# STM32F303CBT6_BTN8962TA_V1_0.net
KiCad netlist of a schematic drawn in EAGLE
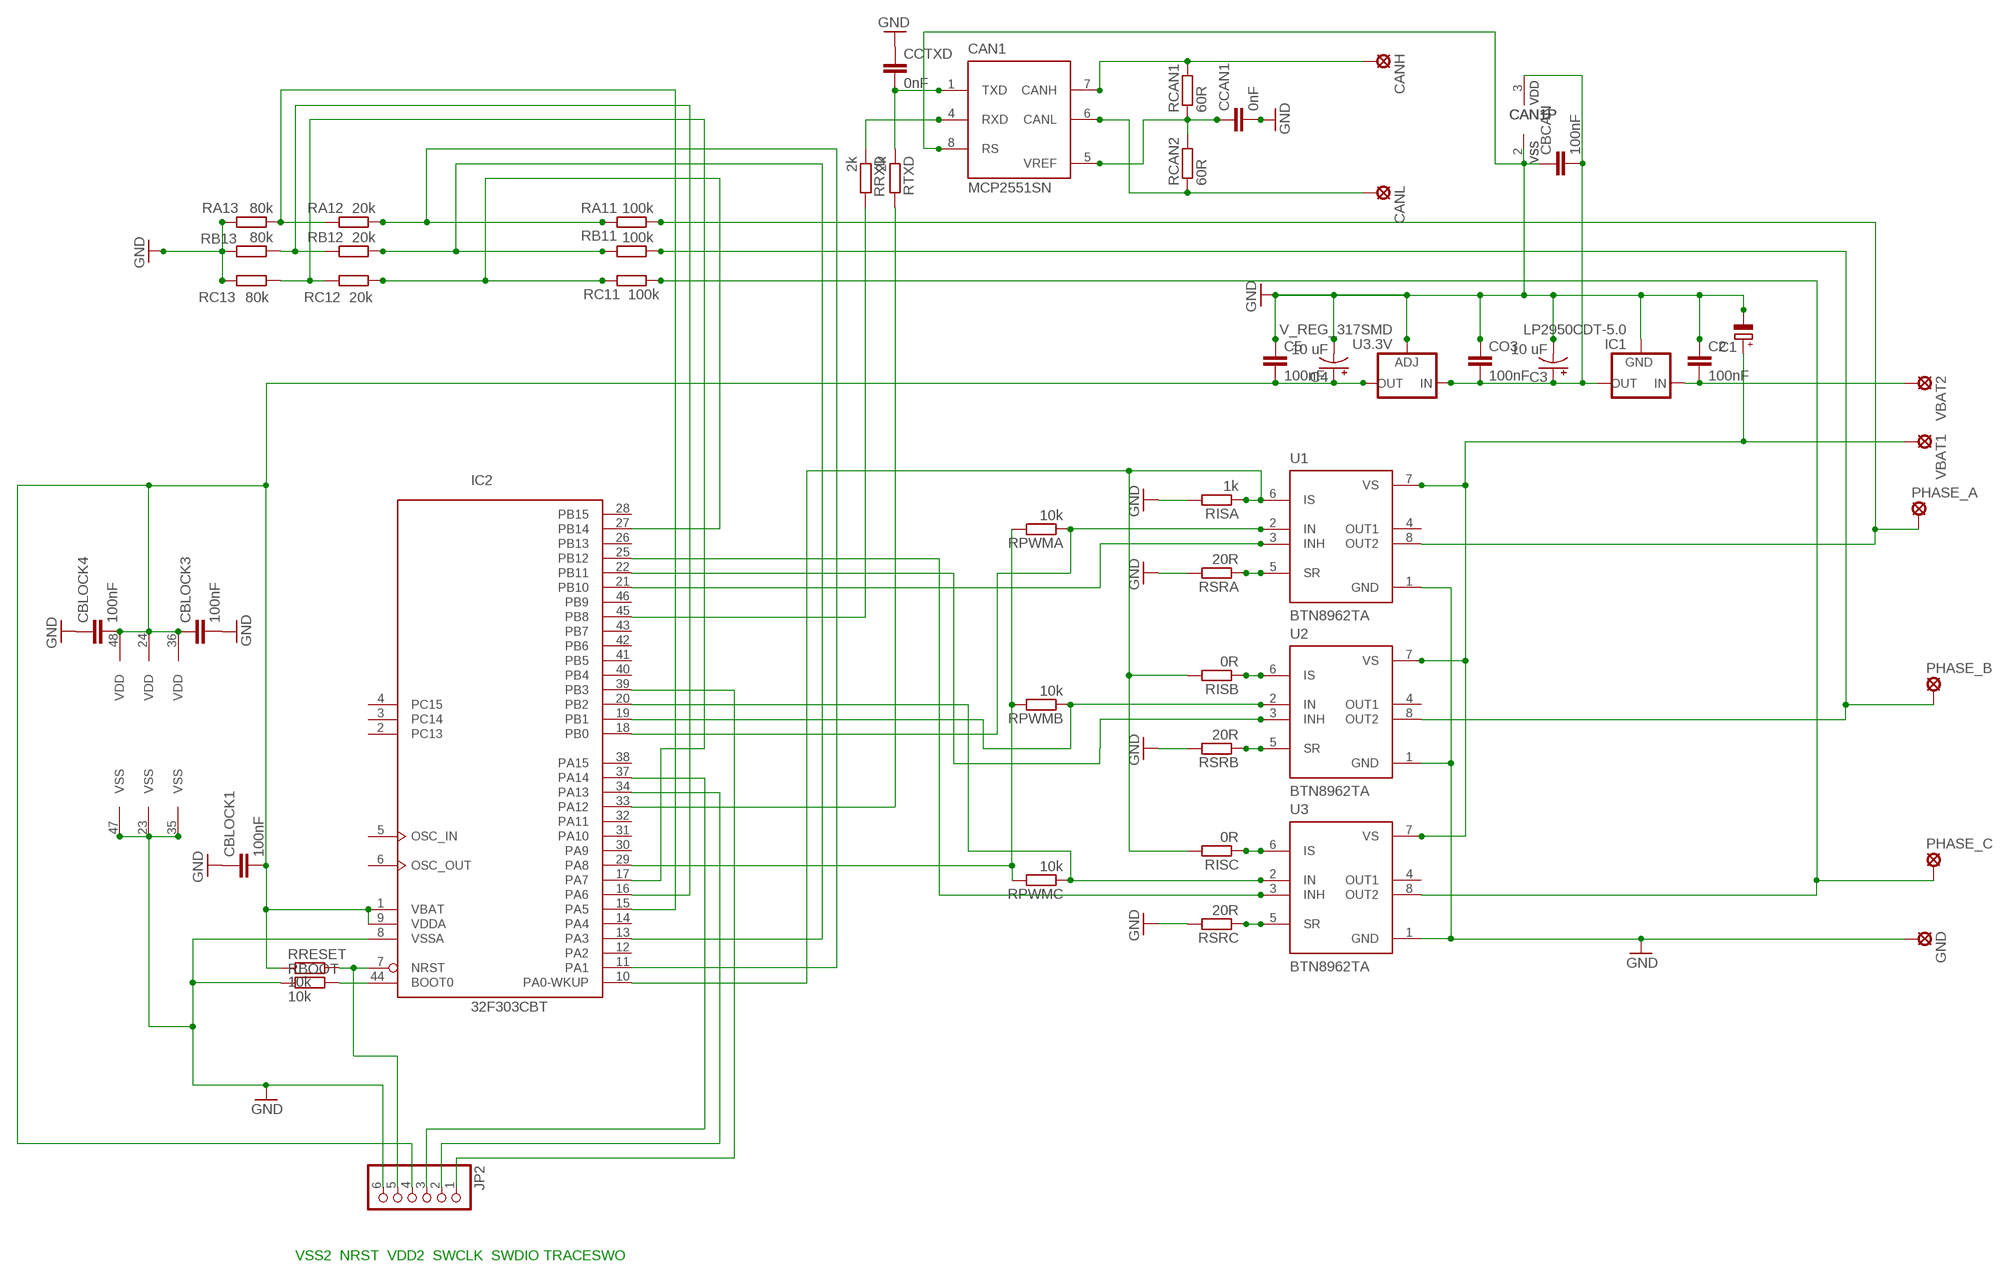
[diagram p0: schematic, sheet 1]

(export (version "E")
  (design (tool "Eeschema 10.0.6"))
  (components
    (comp (ref "C1")
      (value "CPOL-EUE3.5-10")
      (footprint "eagle-import:E3,5-10")
      (libsource (lib "eagle-import") (part "CPOL-EUE3.5-10"))
    )
    (comp (ref "C2")
      (value "100nF")
      (footprint "eagle-import:C0805")
      (libsource (lib "eagle-import") (part "C-EUC0805"))
    )
    (comp (ref "C3")
      (value "10 uF")
      (footprint "eagle-import:PANASONIC_D")
      (libsource (lib "eagle-import") (part "CAP_POLD"))
    )
    (comp (ref "C4")
      (value "10 uF")
      (footprint "eagle-import:PANASONIC_D")
      (libsource (lib "eagle-import") (part "CAP_POLD"))
    )
    (comp (ref "C5")
      (value "100nF")
      (footprint "eagle-import:C0805")
      (libsource (lib "eagle-import") (part "C-EUC0805"))
    )
    (comp (ref "CAN1")
      (value "MCP2551SN")
      (footprint "eagle-import:SO-08")
      (libsource (lib "eagle-import") (part "MCP2551SN"))
    )
    (comp (ref "CANH")
      (value "LSP10")
      (footprint "eagle-import:LSP10")
      (libsource (lib "eagle-import") (part "LSP10"))
    )
    (comp (ref "CANL")
      (value "LSP10")
      (footprint "eagle-import:LSP10")
      (libsource (lib "eagle-import") (part "LSP10"))
    )
    (comp (ref "CBCAN")
      (value "100nF")
      (footprint "eagle-import:C0805")
      (libsource (lib "eagle-import") (part "C-EUC0805"))
    )
    (comp (ref "CBLOCK1")
      (value "100nF")
      (footprint "eagle-import:C0805")
      (libsource (lib "eagle-import") (part "C-EUC0805"))
    )
    (comp (ref "CBLOCK3")
      (value "100nF")
      (footprint "eagle-import:C0805")
      (libsource (lib "eagle-import") (part "C-EUC0805"))
    )
    (comp (ref "CBLOCK4")
      (value "100nF")
      (footprint "eagle-import:C0805")
      (libsource (lib "eagle-import") (part "C-EUC0805"))
    )
    (comp (ref "CCAN1")
      (value "0nF")
      (footprint "eagle-import:C0805")
      (libsource (lib "eagle-import") (part "C-EUC0805"))
    )
    (comp (ref "CCTXD")
      (value "0nF")
      (footprint "eagle-import:C0805")
      (libsource (lib "eagle-import") (part "C-EUC0805"))
    )
    (comp (ref "CO3")
      (value "100nF")
      (footprint "eagle-import:C0805")
      (libsource (lib "eagle-import") (part "C-EUC0805"))
    )
    (comp (ref "GND")
      (value "SE14")
      (footprint "eagle-import:SE14")
      (libsource (lib "eagle-import") (part "SE14"))
    )
    (comp (ref "IC1")
      (value "LP2950CDT-5.0")
      (footprint "eagle-import:DPACK")
      (libsource (lib "eagle-import") (part "LP2950?CDT-5.0"))
    )
    (comp (ref "IC2")
      (value "32F303CBT")
      (footprint "eagle-import:LQFP48")
      (libsource (lib "eagle-import") (part "STM32F303CTB"))
    )
    (comp (ref "JP2")
      (value "PINHD-1X6")
      (footprint "eagle-import:1X06")
      (libsource (lib "eagle-import") (part "PINHD-1X6"))
    )
    (comp (ref "PHASE_A")
      (value "SE14")
      (footprint "eagle-import:SE14")
      (libsource (lib "eagle-import") (part "SE14"))
    )
    (comp (ref "PHASE_B")
      (value "SE14")
      (footprint "eagle-import:SE14")
      (libsource (lib "eagle-import") (part "SE14"))
    )
    (comp (ref "PHASE_C")
      (value "SE14")
      (footprint "eagle-import:SE14")
      (libsource (lib "eagle-import") (part "SE14"))
    )
    (comp (ref "RA11")
      (value "100k")
      (footprint "eagle-import:R0805")
      (libsource (lib "eagle-import") (part "R-EU_R0805"))
    )
    (comp (ref "RA12")
      (value "20k")
      (footprint "eagle-import:R0805")
      (libsource (lib "eagle-import") (part "R-EU_R0805"))
    )
    (comp (ref "RA13")
      (value "80k")
      (footprint "eagle-import:R0805")
      (libsource (lib "eagle-import") (part "R-EU_R0805"))
    )
    (comp (ref "RB11")
      (value "100k")
      (footprint "eagle-import:R0805")
      (libsource (lib "eagle-import") (part "R-EU_R0805"))
    )
    (comp (ref "RB12")
      (value "20k")
      (footprint "eagle-import:R0805")
      (libsource (lib "eagle-import") (part "R-EU_R0805"))
    )
    (comp (ref "RB13")
      (value "80k")
      (footprint "eagle-import:R0805")
      (libsource (lib "eagle-import") (part "R-EU_R0805"))
    )
    (comp (ref "RBOOT")
      (value "10k")
      (footprint "eagle-import:R0805")
      (libsource (lib "eagle-import") (part "R-EU_R0805"))
    )
    (comp (ref "RC11")
      (value "100k")
      (footprint "eagle-import:R0805")
      (libsource (lib "eagle-import") (part "R-EU_R0805"))
    )
    (comp (ref "RC12")
      (value "20k")
      (footprint "eagle-import:R0805")
      (libsource (lib "eagle-import") (part "R-EU_R0805"))
    )
    (comp (ref "RC13")
      (value "80k")
      (footprint "eagle-import:R0805")
      (libsource (lib "eagle-import") (part "R-EU_R0805"))
    )
    (comp (ref "RCAN1")
      (value "60R")
      (footprint "eagle-import:R0805")
      (libsource (lib "eagle-import") (part "R-EU_R0805"))
    )
    (comp (ref "RCAN2")
      (value "60R")
      (footprint "eagle-import:R0805")
      (libsource (lib "eagle-import") (part "R-EU_R0805"))
    )
    (comp (ref "RISA")
      (value "1k")
      (footprint "eagle-import:R0805")
      (libsource (lib "eagle-import") (part "R-EU_R0805"))
    )
    (comp (ref "RISB")
      (value "0R")
      (footprint "eagle-import:R0805")
      (libsource (lib "eagle-import") (part "R-EU_R0805"))
    )
    (comp (ref "RISC")
      (value "0R")
      (footprint "eagle-import:R0805")
      (libsource (lib "eagle-import") (part "R-EU_R0805"))
    )
    (comp (ref "RPWMA")
      (value "10k")
      (footprint "eagle-import:R0805")
      (libsource (lib "eagle-import") (part "R-EU_R0805"))
    )
    (comp (ref "RPWMB")
      (value "10k")
      (footprint "eagle-import:R0805")
      (libsource (lib "eagle-import") (part "R-EU_R0805"))
    )
    (comp (ref "RPWMC")
      (value "10k")
      (footprint "eagle-import:R0805")
      (libsource (lib "eagle-import") (part "R-EU_R0805"))
    )
    (comp (ref "RRESET")
      (value "10k")
      (footprint "eagle-import:R0805")
      (libsource (lib "eagle-import") (part "R-EU_R0805"))
    )
    (comp (ref "RRXD")
      (value "2k")
      (footprint "eagle-import:R0805")
      (libsource (lib "eagle-import") (part "R-EU_R0805"))
    )
    (comp (ref "RSRA")
      (value "20R")
      (footprint "eagle-import:R0805")
      (libsource (lib "eagle-import") (part "R-EU_R0805"))
    )
    (comp (ref "RSRB")
      (value "20R")
      (footprint "eagle-import:R0805")
      (libsource (lib "eagle-import") (part "R-EU_R0805"))
    )
    (comp (ref "RSRC")
      (value "20R")
      (footprint "eagle-import:R0805")
      (libsource (lib "eagle-import") (part "R-EU_R0805"))
    )
    (comp (ref "RTXD")
      (value "2k")
      (footprint "eagle-import:R0805")
      (libsource (lib "eagle-import") (part "R-EU_R0805"))
    )
    (comp (ref "U1")
      (value "BTN8962TA")
      (footprint "eagle-import:TO127P1500X440-8N-1")
      (libsource (lib "eagle-import") (part "BTN8962TA"))
    )
    (comp (ref "U2")
      (value "BTN8962TA")
      (footprint "eagle-import:TO127P1500X440-8N-1")
      (libsource (lib "eagle-import") (part "BTN8962TA"))
    )
    (comp (ref "U3")
      (value "BTN8962TA")
      (footprint "eagle-import:TO127P1500X440-8N-1")
      (libsource (lib "eagle-import") (part "BTN8962TA"))
    )
    (comp (ref "U3.3V")
      (value "V_REG_317SMD")
      (footprint "eagle-import:SOT223")
      (libsource (lib "eagle-import") (part "V_REG_317SMD"))
    )
    (comp (ref "VBAT1")
      (value "SE14")
      (footprint "eagle-import:SE14")
      (libsource (lib "eagle-import") (part "SE14"))
    )
    (comp (ref "VBAT2")
      (value "SE14")
      (footprint "eagle-import:SE14")
      (libsource (lib "eagle-import") (part "SE14"))
    )
  )
  (nets
    (net (code "1") (name "GND") (class "Default")
      (node (ref "C1") (pin "-") (pinfunction "-_-") (pintype "passive"))
      (node (ref "C2") (pin "1") (pinfunction "1_1") (pintype "passive"))
      (node (ref "C3") (pin "-") (pinfunction "-_-") (pintype "passive"))
      (node (ref "C4") (pin "-") (pinfunction "-_-") (pintype "passive"))
      (node (ref "C5") (pin "1") (pinfunction "1_1") (pintype "passive"))
      (node (ref "CAN1") (pin "2") (pinfunction "VSS_2") (pintype "power_in"))
      (node (ref "CAN1") (pin "8") (pinfunction "RS_8") (pintype "input"))
      (node (ref "CBCAN") (pin "1") (pinfunction "1_1") (pintype "passive"))
      (node (ref "CBLOCK1") (pin "1") (pinfunction "1_1") (pintype "passive"))
      (node (ref "CBLOCK3") (pin "2") (pinfunction "2_2") (pintype "passive"))
      (node (ref "CBLOCK4") (pin "1") (pinfunction "1_1") (pintype "passive"))
      (node (ref "CCAN1") (pin "2") (pinfunction "2_2") (pintype "passive"))
      (node (ref "CCTXD") (pin "1") (pinfunction "1_1") (pintype "passive"))
      (node (ref "CO3") (pin "1") (pinfunction "1_1") (pintype "passive"))
      (node (ref "GND") (pin "MP") (pinfunction "MP_MP") (pintype "passive"))
      (node (ref "IC1") (pin "4") (pinfunction "GND_4") (pintype "input"))
      (node (ref "IC2") (pin "23") (pinfunction "VSS_23") (pintype "power_in"))
      (node (ref "IC2") (pin "35") (pinfunction "VSS_35") (pintype "power_in"))
      (node (ref "IC2") (pin "47") (pinfunction "VSS_47") (pintype "power_in"))
      (node (ref "IC2") (pin "8") (pinfunction "VSSA_8") (pintype "power_in"))
      (node (ref "JP2") (pin "6") (pinfunction "6_6") (pintype "passive"))
      (node (ref "RA13") (pin "2") (pinfunction "2_2") (pintype "passive"))
      (node (ref "RB13") (pin "2") (pinfunction "2_2") (pintype "passive"))
      (node (ref "RBOOT") (pin "1") (pinfunction "1_1") (pintype "passive"))
      (node (ref "RC13") (pin "2") (pinfunction "2_2") (pintype "passive"))
      (node (ref "RISA") (pin "2") (pinfunction "2_2") (pintype "passive"))
      (node (ref "RSRA") (pin "2") (pinfunction "2_2") (pintype "passive"))
      (node (ref "RSRB") (pin "2") (pinfunction "2_2") (pintype "passive"))
      (node (ref "RSRC") (pin "2") (pinfunction "2_2") (pintype "passive"))
      (node (ref "U1") (pin "1") (pinfunction "GND_1") (pintype "power_in"))
      (node (ref "U2") (pin "1") (pinfunction "GND_1") (pintype "power_in"))
      (node (ref "U3") (pin "1") (pinfunction "GND_1") (pintype "power_in"))
      (node (ref "U3.3V") (pin "1") (pinfunction "ADJ_1") (pintype "input"))
    )
    (net (code "2") (name "Net-(CAN1A-CANH)") (class "Default")
      (node (ref "CAN1") (pin "7") (pinfunction "CANH_7") (pintype "bidirectional"))
      (node (ref "CANH") (pin "MP") (pinfunction "MP_MP") (pintype "passive"))
      (node (ref "RCAN1") (pin "2") (pinfunction "2_2") (pintype "passive"))
    )
    (net (code "3") (name "Net-(CAN1A-CANL)") (class "Default")
      (node (ref "CAN1") (pin "6") (pinfunction "CANL_6") (pintype "bidirectional"))
      (node (ref "CANL") (pin "MP") (pinfunction "MP_MP") (pintype "passive"))
      (node (ref "RCAN2") (pin "1") (pinfunction "1_1") (pintype "passive"))
    )
    (net (code "4") (name "Net-(CAN1A-RXD)") (class "Default")
      (node (ref "CAN1") (pin "4") (pinfunction "RXD_4") (pintype "output"))
      (node (ref "RRXD") (pin "1") (pinfunction "1_1") (pintype "passive"))
    )
    (net (code "5") (name "Net-(CAN1A-TXD)") (class "Default")
      (node (ref "CAN1") (pin "1") (pinfunction "TXD_1") (pintype "input"))
      (node (ref "CCTXD") (pin "2") (pinfunction "2_2") (pintype "passive"))
      (node (ref "RTXD") (pin "1") (pinfunction "1_1") (pintype "passive"))
    )
    (net (code "6") (name "Net-(CAN1A-VREF)") (class "Default")
      (node (ref "CAN1") (pin "5") (pinfunction "VREF_5") (pintype "power_in"))
      (node (ref "CCAN1") (pin "1") (pinfunction "1_1") (pintype "passive"))
      (node (ref "RCAN1") (pin "1") (pinfunction "1_1") (pintype "passive"))
      (node (ref "RCAN2") (pin "2") (pinfunction "2_2") (pintype "passive"))
    )
    (net (code "7") (name "Net-(CAN1B-VDD)") (class "Default")
      (node (ref "C3") (pin "+") (pinfunction "+_+") (pintype "passive"))
      (node (ref "CAN1") (pin "3") (pinfunction "VDD_3") (pintype "power_in"))
      (node (ref "CBCAN") (pin "2") (pinfunction "2_2") (pintype "passive"))
      (node (ref "CO3") (pin "2") (pinfunction "2_2") (pintype "passive"))
      (node (ref "IC1") (pin "3") (pinfunction "OUT_3") (pintype "passive"))
      (node (ref "U3.3V") (pin "3") (pinfunction "IN_3") (pintype "input"))
    )
    (net (code "8") (name "Net-(IC1-IN)") (class "Default")
      (node (ref "C2") (pin "2") (pinfunction "2_2") (pintype "passive"))
      (node (ref "IC1") (pin "1") (pinfunction "IN_1") (pintype "input"))
      (node (ref "VBAT2") (pin "MP") (pinfunction "MP_MP") (pintype "passive"))
    )
    (net (code "9") (name "Net-(IC2A-BOOT0)") (class "Default")
      (node (ref "IC2") (pin "44") (pinfunction "BOOT0_44") (pintype "input"))
      (node (ref "RBOOT") (pin "2") (pinfunction "2_2") (pintype "passive"))
    )
    (net (code "10") (name "Net-(IC2A-NRST)") (class "Default")
      (node (ref "IC2") (pin "7") (pinfunction "NRST_7") (pintype "bidirectional"))
      (node (ref "JP2") (pin "5") (pinfunction "5_5") (pintype "passive"))
      (node (ref "RRESET") (pin "2") (pinfunction "2_2") (pintype "passive"))
    )
    (net (code "11") (name "Net-(IC2A-PA0-WKUP)") (class "Default")
      (node (ref "IC2") (pin "10") (pinfunction "PA0-WKUP_10") (pintype "bidirectional"))
      (node (ref "RISA") (pin "1") (pinfunction "1_1") (pintype "passive"))
      (node (ref "RISB") (pin "2") (pinfunction "2_2") (pintype "passive"))
      (node (ref "RISC") (pin "2") (pinfunction "2_2") (pintype "passive"))
      (node (ref "U1") (pin "6") (pinfunction "IS_6") (pintype "output"))
    )
    (net (code "12") (name "Net-(IC2A-PA1)") (class "Default")
      (node (ref "IC2") (pin "11") (pinfunction "PA1_11") (pintype "bidirectional"))
      (node (ref "RA11") (pin "2") (pinfunction "2_2") (pintype "passive"))
      (node (ref "RA12") (pin "1") (pinfunction "1_1") (pintype "passive"))
    )
    (net (code "13") (name "Net-(IC2A-PA3)") (class "Default")
      (node (ref "IC2") (pin "13") (pinfunction "PA3_13") (pintype "bidirectional"))
      (node (ref "RB11") (pin "2") (pinfunction "2_2") (pintype "passive"))
      (node (ref "RB12") (pin "1") (pinfunction "1_1") (pintype "passive"))
    )
    (net (code "14") (name "Net-(IC2A-PA5)") (class "Default")
      (node (ref "IC2") (pin "15") (pinfunction "PA5_15") (pintype "bidirectional"))
      (node (ref "RA12") (pin "2") (pinfunction "2_2") (pintype "passive"))
      (node (ref "RA13") (pin "1") (pinfunction "1_1") (pintype "passive"))
    )
    (net (code "15") (name "Net-(IC2A-PA6)") (class "Default")
      (node (ref "IC2") (pin "16") (pinfunction "PA6_16") (pintype "bidirectional"))
      (node (ref "RB12") (pin "2") (pinfunction "2_2") (pintype "passive"))
      (node (ref "RB13") (pin "1") (pinfunction "1_1") (pintype "passive"))
    )
    (net (code "16") (name "Net-(IC2A-PA7)") (class "Default")
      (node (ref "IC2") (pin "17") (pinfunction "PA7_17") (pintype "bidirectional"))
      (node (ref "RC12") (pin "2") (pinfunction "2_2") (pintype "passive"))
      (node (ref "RC13") (pin "1") (pinfunction "1_1") (pintype "passive"))
    )
    (net (code "17") (name "Net-(IC2A-PA8)") (class "Default")
      (node (ref "IC2") (pin "29") (pinfunction "PA8_29") (pintype "bidirectional"))
      (node (ref "RPWMA") (pin "2") (pinfunction "2_2") (pintype "passive"))
      (node (ref "RPWMB") (pin "2") (pinfunction "2_2") (pintype "passive"))
      (node (ref "RPWMC") (pin "2") (pinfunction "2_2") (pintype "passive"))
    )
    (net (code "18") (name "Net-(IC2A-PA12)") (class "Default")
      (node (ref "IC2") (pin "33") (pinfunction "PA12_33") (pintype "bidirectional"))
      (node (ref "RTXD") (pin "2") (pinfunction "2_2") (pintype "passive"))
    )
    (net (code "19") (name "Net-(IC2A-PA13)") (class "Default")
      (node (ref "IC2") (pin "34") (pinfunction "PA13_34") (pintype "bidirectional"))
      (node (ref "JP2") (pin "2") (pinfunction "2_2") (pintype "passive"))
    )
    (net (code "20") (name "Net-(IC2A-PA14)") (class "Default")
      (node (ref "IC2") (pin "37") (pinfunction "PA14_37") (pintype "bidirectional"))
      (node (ref "JP2") (pin "3") (pinfunction "3_3") (pintype "passive"))
    )
    (net (code "21") (name "Net-(IC2A-PB0)") (class "Default")
      (node (ref "IC2") (pin "18") (pinfunction "PB0_18") (pintype "bidirectional"))
      (node (ref "RPWMA") (pin "1") (pinfunction "1_1") (pintype "passive"))
      (node (ref "U1") (pin "2") (pinfunction "IN_2") (pintype "input"))
    )
    (net (code "22") (name "Net-(IC2A-PB1)") (class "Default")
      (node (ref "IC2") (pin "19") (pinfunction "PB1_19") (pintype "bidirectional"))
      (node (ref "RPWMB") (pin "1") (pinfunction "1_1") (pintype "passive"))
      (node (ref "U2") (pin "2") (pinfunction "IN_2") (pintype "input"))
    )
    (net (code "23") (name "Net-(IC2A-PB2)") (class "Default")
      (node (ref "IC2") (pin "20") (pinfunction "PB2_20") (pintype "bidirectional"))
      (node (ref "RPWMC") (pin "1") (pinfunction "1_1") (pintype "passive"))
      (node (ref "U3") (pin "2") (pinfunction "IN_2") (pintype "input"))
    )
    (net (code "24") (name "Net-(IC2A-PB3)") (class "Default")
      (node (ref "IC2") (pin "39") (pinfunction "PB3_39") (pintype "bidirectional"))
      (node (ref "JP2") (pin "1") (pinfunction "1_1") (pintype "passive"))
    )
    (net (code "25") (name "Net-(IC2A-PB8)") (class "Default")
      (node (ref "IC2") (pin "45") (pinfunction "PB8_45") (pintype "bidirectional"))
      (node (ref "RRXD") (pin "2") (pinfunction "2_2") (pintype "passive"))
    )
    (net (code "26") (name "Net-(IC2A-PB10)") (class "Default")
      (node (ref "IC2") (pin "21") (pinfunction "PB10_21") (pintype "bidirectional"))
      (node (ref "U1") (pin "3") (pinfunction "INH_3") (pintype "input"))
    )
    (net (code "27") (name "Net-(IC2A-PB11)") (class "Default")
      (node (ref "IC2") (pin "22") (pinfunction "PB11_22") (pintype "bidirectional"))
      (node (ref "U2") (pin "3") (pinfunction "INH_3") (pintype "input"))
    )
    (net (code "28") (name "Net-(IC2A-PB12)") (class "Default")
      (node (ref "IC2") (pin "25") (pinfunction "PB12_25") (pintype "bidirectional"))
      (node (ref "U3") (pin "3") (pinfunction "INH_3") (pintype "input"))
    )
    (net (code "29") (name "Net-(IC2A-PB14)") (class "Default")
      (node (ref "IC2") (pin "27") (pinfunction "PB14_27") (pintype "bidirectional"))
      (node (ref "RC11") (pin "2") (pinfunction "2_2") (pintype "passive"))
      (node (ref "RC12") (pin "1") (pinfunction "1_1") (pintype "passive"))
    )
    (net (code "30") (name "Net-(IC2A-VBAT)") (class "Default")
      (node (ref "C4") (pin "+") (pinfunction "+_+") (pintype "passive"))
      (node (ref "C5") (pin "2") (pinfunction "2_2") (pintype "passive"))
      (node (ref "CBLOCK1") (pin "2") (pinfunction "2_2") (pintype "passive"))
      (node (ref "CBLOCK3") (pin "1") (pinfunction "1_1") (pintype "passive"))
      (node (ref "CBLOCK4") (pin "2") (pinfunction "2_2") (pintype "passive"))
      (node (ref "IC2") (pin "1") (pinfunction "VBAT_1") (pintype "power_in"))
      (node (ref "IC2") (pin "24") (pinfunction "VDD_24") (pintype "power_in"))
      (node (ref "IC2") (pin "36") (pinfunction "VDD_36") (pintype "power_in"))
      (node (ref "IC2") (pin "48") (pinfunction "VDD_48") (pintype "power_in"))
      (node (ref "IC2") (pin "9") (pinfunction "VDDA_9") (pintype "power_in"))
      (node (ref "JP2") (pin "4") (pinfunction "4_4") (pintype "passive"))
      (node (ref "RRESET") (pin "1") (pinfunction "1_1") (pintype "passive"))
      (node (ref "U3.3V") (pin "2") (pinfunction "OUT_2") (pintype "output"))
    )
    (net (code "31") (name "Net-(U1-OUT2)") (class "Default")
      (node (ref "PHASE_A") (pin "MP") (pinfunction "MP_MP") (pintype "passive"))
      (node (ref "RA11") (pin "1") (pinfunction "1_1") (pintype "passive"))
      (node (ref "U1") (pin "8") (pinfunction "OUT2_8") (pintype "output"))
    )
    (net (code "32") (name "Net-(U1-SR)") (class "Default")
      (node (ref "RSRA") (pin "1") (pinfunction "1_1") (pintype "passive"))
      (node (ref "U1") (pin "5") (pinfunction "SR_5") (pintype "input"))
    )
    (net (code "33") (name "Net-(U1-VS)") (class "Default")
      (node (ref "C1") (pin "+") (pinfunction "+_+") (pintype "passive"))
      (node (ref "U1") (pin "7") (pinfunction "VS_7") (pintype "power_in"))
      (node (ref "U2") (pin "7") (pinfunction "VS_7") (pintype "power_in"))
      (node (ref "U3") (pin "7") (pinfunction "VS_7") (pintype "power_in"))
      (node (ref "VBAT1") (pin "MP") (pinfunction "MP_MP") (pintype "passive"))
    )
    (net (code "34") (name "Net-(U2-IS)") (class "Default")
      (node (ref "RISB") (pin "1") (pinfunction "1_1") (pintype "passive"))
      (node (ref "U2") (pin "6") (pinfunction "IS_6") (pintype "output"))
    )
    (net (code "35") (name "Net-(U2-OUT2)") (class "Default")
      (node (ref "PHASE_B") (pin "MP") (pinfunction "MP_MP") (pintype "passive"))
      (node (ref "RB11") (pin "1") (pinfunction "1_1") (pintype "passive"))
      (node (ref "U2") (pin "8") (pinfunction "OUT2_8") (pintype "output"))
    )
    (net (code "36") (name "Net-(U2-SR)") (class "Default")
      (node (ref "RSRB") (pin "1") (pinfunction "1_1") (pintype "passive"))
      (node (ref "U2") (pin "5") (pinfunction "SR_5") (pintype "input"))
    )
    (net (code "37") (name "Net-(U3-IS)") (class "Default")
      (node (ref "RISC") (pin "1") (pinfunction "1_1") (pintype "passive"))
      (node (ref "U3") (pin "6") (pinfunction "IS_6") (pintype "output"))
    )
    (net (code "38") (name "Net-(U3-OUT2)") (class "Default")
      (node (ref "PHASE_C") (pin "MP") (pinfunction "MP_MP") (pintype "passive"))
      (node (ref "RC11") (pin "1") (pinfunction "1_1") (pintype "passive"))
      (node (ref "U3") (pin "8") (pinfunction "OUT2_8") (pintype "output"))
    )
    (net (code "39") (name "Net-(U3-SR)") (class "Default")
      (node (ref "RSRC") (pin "1") (pinfunction "1_1") (pintype "passive"))
      (node (ref "U3") (pin "5") (pinfunction "SR_5") (pintype "input"))
    )
    (net (code "40") (name "unconnected-(IC2A-OSC_IN-Pad5)") (class "Default")
      (node (ref "IC2") (pin "5") (pinfunction "OSC_IN_5") (pintype "bidirectional"))
    )
    (net (code "41") (name "unconnected-(IC2A-OSC_OUT-Pad6)") (class "Default")
      (node (ref "IC2") (pin "6") (pinfunction "OSC_OUT_6") (pintype "bidirectional"))
    )
    (net (code "42") (name "unconnected-(IC2A-PA2-Pad12)") (class "Default")
      (node (ref "IC2") (pin "12") (pinfunction "PA2_12") (pintype "bidirectional"))
    )
    (net (code "43") (name "unconnected-(IC2A-PA4-Pad14)") (class "Default")
      (node (ref "IC2") (pin "14") (pinfunction "PA4_14") (pintype "bidirectional"))
    )
    (net (code "44") (name "unconnected-(IC2A-PA9-Pad30)") (class "Default")
      (node (ref "IC2") (pin "30") (pinfunction "PA9_30") (pintype "bidirectional"))
    )
    (net (code "45") (name "unconnected-(IC2A-PA10-Pad31)") (class "Default")
      (node (ref "IC2") (pin "31") (pinfunction "PA10_31") (pintype "bidirectional"))
    )
    (net (code "46") (name "unconnected-(IC2A-PA11-Pad32)") (class "Default")
      (node (ref "IC2") (pin "32") (pinfunction "PA11_32") (pintype "bidirectional"))
    )
    (net (code "47") (name "unconnected-(IC2A-PA15-Pad38)") (class "Default")
      (node (ref "IC2") (pin "38") (pinfunction "PA15_38") (pintype "bidirectional"))
    )
    (net (code "48") (name "unconnected-(IC2A-PB4-Pad40)") (class "Default")
      (node (ref "IC2") (pin "40") (pinfunction "PB4_40") (pintype "bidirectional"))
    )
    (net (code "49") (name "unconnected-(IC2A-PB5-Pad41)") (class "Default")
      (node (ref "IC2") (pin "41") (pinfunction "PB5_41") (pintype "bidirectional"))
    )
    (net (code "50") (name "unconnected-(IC2A-PB6-Pad42)") (class "Default")
      (node (ref "IC2") (pin "42") (pinfunction "PB6_42") (pintype "bidirectional"))
    )
    (net (code "51") (name "unconnected-(IC2A-PB7-Pad43)") (class "Default")
      (node (ref "IC2") (pin "43") (pinfunction "PB7_43") (pintype "bidirectional"))
    )
    (net (code "52") (name "unconnected-(IC2A-PB9-Pad46)") (class "Default")
      (node (ref "IC2") (pin "46") (pinfunction "PB9_46") (pintype "bidirectional"))
    )
    (net (code "53") (name "unconnected-(IC2A-PB13-Pad26)") (class "Default")
      (node (ref "IC2") (pin "26") (pinfunction "PB13_26") (pintype "bidirectional"))
    )
    (net (code "54") (name "unconnected-(IC2A-PB15-Pad28)") (class "Default")
      (node (ref "IC2") (pin "28") (pinfunction "PB15_28") (pintype "bidirectional"))
    )
    (net (code "55") (name "unconnected-(IC2A-PC13-Pad2)") (class "Default")
      (node (ref "IC2") (pin "2") (pinfunction "PC13_2") (pintype "bidirectional"))
    )
    (net (code "56") (name "unconnected-(IC2A-PC14-Pad3)") (class "Default")
      (node (ref "IC2") (pin "3") (pinfunction "PC14_3") (pintype "bidirectional"))
    )
    (net (code "57") (name "unconnected-(IC2A-PC15-Pad4)") (class "Default")
      (node (ref "IC2") (pin "4") (pinfunction "PC15_4") (pintype "bidirectional"))
    )
    (net (code "58") (name "unconnected-(U1-OUT1-Pad4)") (class "Default")
      (node (ref "U1") (pin "4") (pinfunction "OUT1_4") (pintype "output"))
    )
    (net (code "59") (name "unconnected-(U2-OUT1-Pad4)") (class "Default")
      (node (ref "U2") (pin "4") (pinfunction "OUT1_4") (pintype "output"))
    )
    (net (code "60") (name "unconnected-(U3-OUT1-Pad4)") (class "Default")
      (node (ref "U3") (pin "4") (pinfunction "OUT1_4") (pintype "output"))
    )
  )
)
